# uv-dosimeter-featherwing-mk-1_3.net
KiCad netlist of a schematic drawn in EAGLE
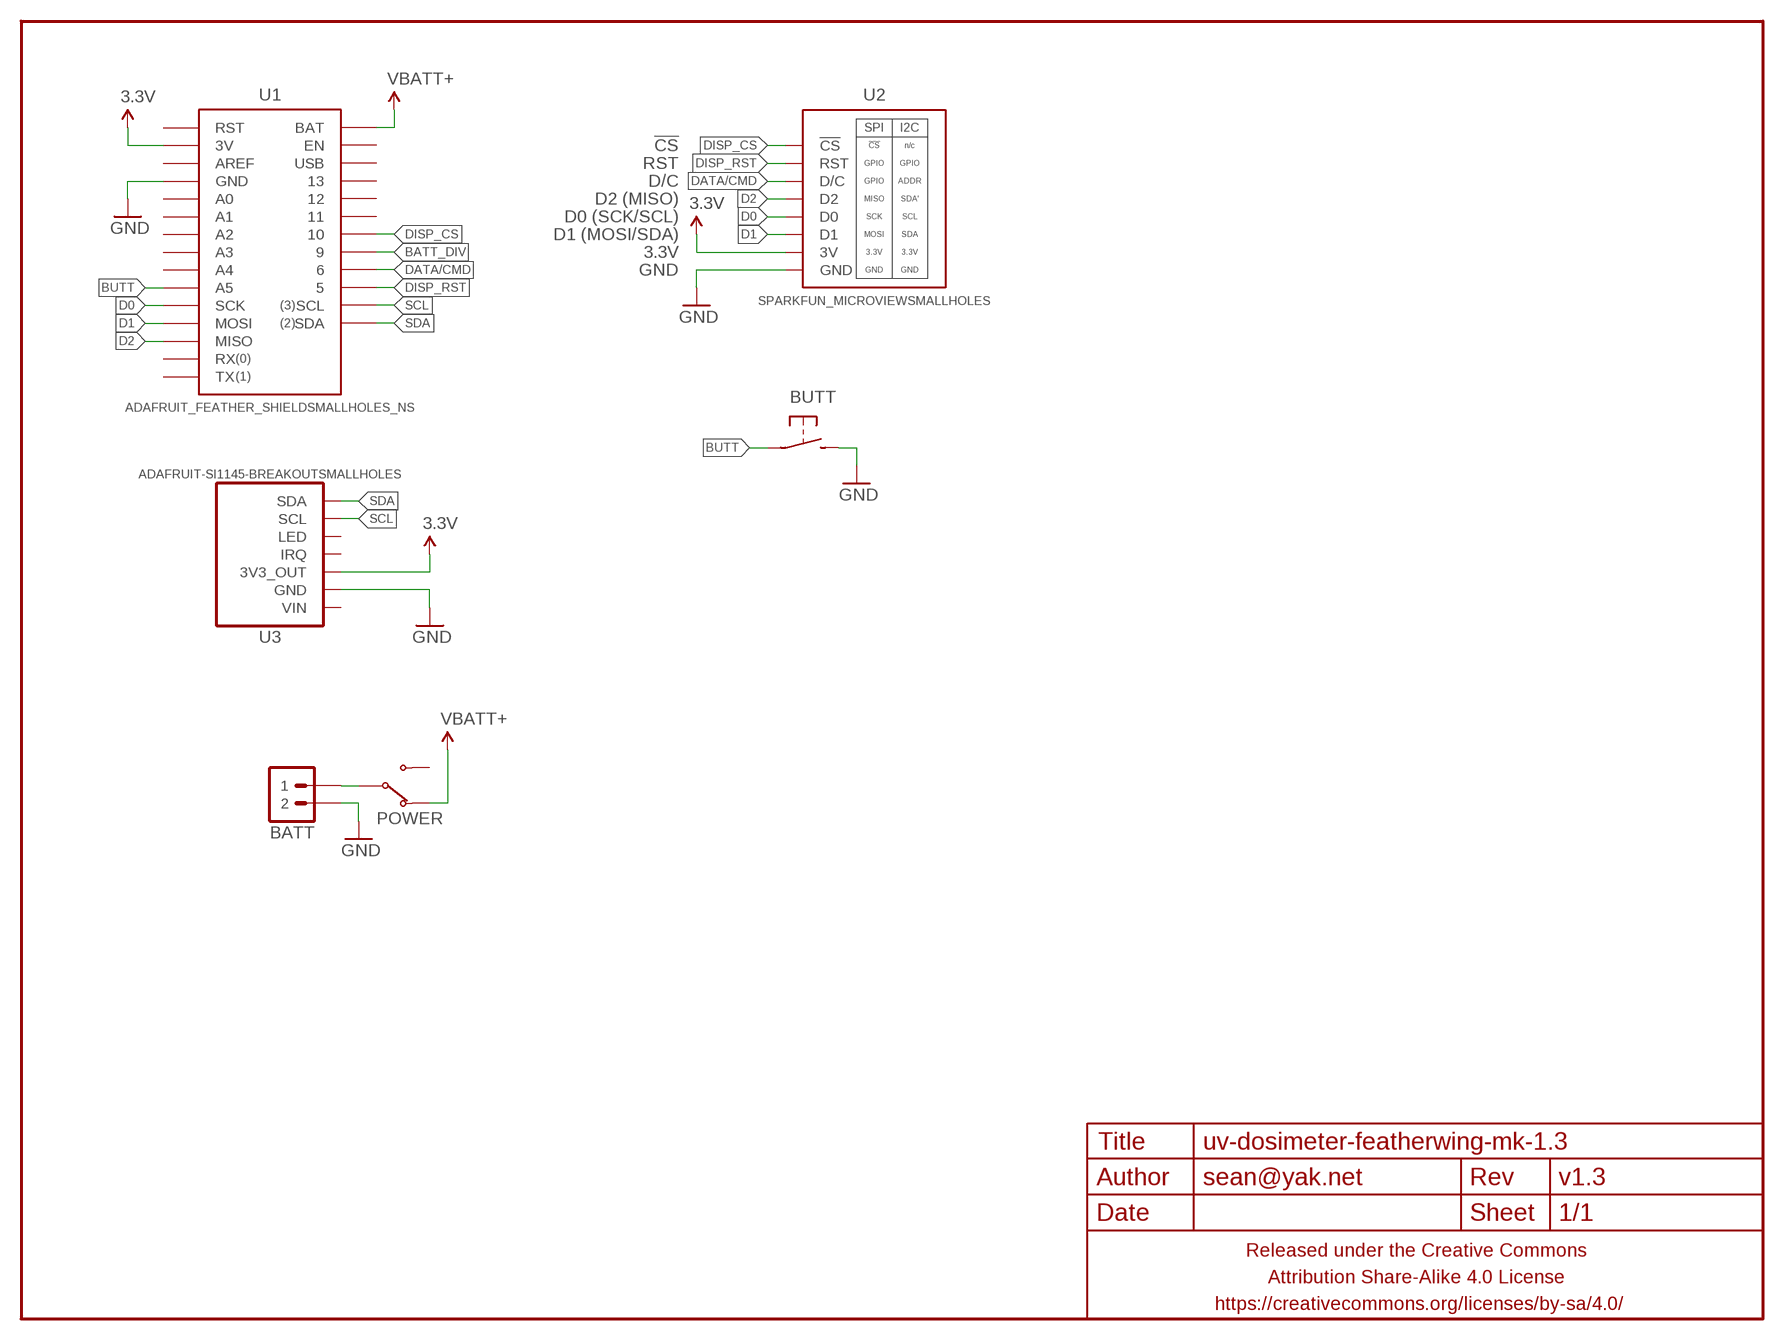
[diagram p0: schematic, sheet 1]

(export (version "E")
  (design (tool "Eeschema 10.0.6"))
  (components
    (comp (ref "BATT")
      (value "M02JST-2MM-SMT")
      (footprint "eagle-import:JST-2-SMD")
      (libsource (lib "eagle-import") (part "M02JST-2MM-SMT"))
    )
    (comp (ref "BUTT")
      (value "SPST-NO-TACT3MM-PTH-SMALL-PADS")
      (footprint "eagle-import:DTS-3-SMALL-PADS")
      (libsource (lib "eagle-import") (part "SPST-NO-TACT3MM-PTH-SMALL-PADS"))
    )
    (comp (ref "FRAME1")
      (value "FRAME-LETTERNO_PACKAGE")
      (footprint "eagle-import:DUMMY")
      (fields (field (name "DESIGNER") "sean@yak.net") (field (name "VERSION") "v1.3"))
      (libsource (lib "eagle-import") (part "FRAME-LETTERNO_PACKAGE"))
    )
    (comp (ref "POWER")
      (value "SWITCH-SPDTPTH-VERT-2.54MM")
      (footprint "eagle-import:SWITCH-SPDT")
      (libsource (lib "eagle-import") (part "SWITCH-SPDTPTH-VERT-2.54MM"))
    )
    (comp (ref "U1")
      (value "ADAFRUIT_FEATHER_SHIELDSMALLHOLES_NS")
      (footprint "eagle-import:ADAFRUIT_FEATHER_SMALLHOLES_NS")
      (libsource (lib "eagle-import") (part "ADAFRUIT_FEATHER_SHIELDSMALLHOLES_NS"))
    )
    (comp (ref "U2")
      (value "SPARKFUN_MICROVIEWSMALLHOLES")
      (footprint "eagle-import:SPARKFUN-MICROVIEW-SMALLHOLES")
      (libsource (lib "eagle-import") (part "SPARKFUN_MICROVIEWSMALLHOLES"))
    )
    (comp (ref "U3")
      (value "ADAFRUIT-SI1145-BREAKOUTSMALLHOLES")
      (footprint "eagle-import:ADAFRUIT-SI1145-BREAKOUT-LESSSILK-SMALLHOLES")
      (libsource (lib "eagle-import") (part "ADAFRUIT-SI1145-BREAKOUTSMALLHOLES"))
    )
  )
  (nets
    (net (code "1") (name "3.3V") (class "Default")
      (node (ref "U1") (pin "3V") (pinfunction "3V_3V") (pintype "bidirectional"))
      (node (ref "U2") (pin "3V") (pinfunction "3V_3V") (pintype "bidirectional"))
      (node (ref "U3") (pin "3V3_OUT") (pinfunction "3V3_OUT_3V3_OUT") (pintype "passive"))
    )
    (net (code "2") (name "BATT_DIV") (class "Default")
      (node (ref "U1") (pin "9") (pinfunction "9_9") (pintype "bidirectional"))
    )
    (net (code "3") (name "BUTT") (class "Default")
      (node (ref "BUTT") (pin "1") (pinfunction "1_1") (pintype "passive"))
      (node (ref "U1") (pin "A5") (pinfunction "A5_A5") (pintype "bidirectional"))
    )
    (net (code "4") (name "D0") (class "Default")
      (node (ref "U1") (pin "SCK") (pinfunction "SCK_SCK") (pintype "bidirectional"))
      (node (ref "U2") (pin "D0") (pinfunction "D0_D0") (pintype "bidirectional"))
    )
    (net (code "5") (name "D1") (class "Default")
      (node (ref "U1") (pin "MOSI") (pinfunction "MOSI_MOSI") (pintype "bidirectional"))
      (node (ref "U2") (pin "D1") (pinfunction "D1_D1") (pintype "bidirectional"))
    )
    (net (code "6") (name "D2") (class "Default")
      (node (ref "U1") (pin "MISO") (pinfunction "MISO_MISO") (pintype "bidirectional"))
      (node (ref "U2") (pin "D2") (pinfunction "D2_D2") (pintype "bidirectional"))
    )
    (net (code "7") (name "DATA{slash}CMD") (class "Default")
      (node (ref "U1") (pin "6") (pinfunction "6_6") (pintype "bidirectional"))
      (node (ref "U2") (pin "D/C") (pinfunction "D/C_D/C") (pintype "bidirectional"))
    )
    (net (code "8") (name "DISP_CS") (class "Default")
      (node (ref "U1") (pin "10") (pinfunction "10_10") (pintype "bidirectional"))
      (node (ref "U2") (pin "CS") (pinfunction "~{CS}_CS") (pintype "bidirectional"))
    )
    (net (code "9") (name "DISP_RST") (class "Default")
      (node (ref "U1") (pin "5") (pinfunction "5_5") (pintype "bidirectional"))
      (node (ref "U2") (pin "RST") (pinfunction "RST_RST") (pintype "bidirectional"))
    )
    (net (code "10") (name "GND") (class "Default")
      (node (ref "BATT") (pin "1") (pinfunction "2_1") (pintype "passive"))
      (node (ref "BUTT") (pin "2") (pinfunction "2_2") (pintype "passive"))
      (node (ref "U1") (pin "GND@0") (pinfunction "GND_GND@0") (pintype "bidirectional"))
      (node (ref "U1") (pin "GND@1") (pinfunction "GND_GND@1") (pintype "bidirectional"))
      (node (ref "U2") (pin "GND") (pinfunction "GND_GND") (pintype "bidirectional"))
      (node (ref "U3") (pin "GND") (pinfunction "GND_GND") (pintype "passive"))
    )
    (net (code "11") (name "Net-(BATT-1)") (class "Default")
      (node (ref "BATT") (pin "2") (pinfunction "1_2") (pintype "passive"))
      (node (ref "POWER") (pin "2") (pinfunction "COM_2") (pintype "passive"))
    )
    (net (code "12") (name "SCL") (class "Default")
      (node (ref "U1") (pin "SCL") (pinfunction "SCL_SCL") (pintype "bidirectional"))
      (node (ref "U3") (pin "SCL") (pinfunction "SCL_SCL") (pintype "passive"))
    )
    (net (code "13") (name "SDA") (class "Default")
      (node (ref "U1") (pin "SDA") (pinfunction "SDA_SDA") (pintype "bidirectional"))
      (node (ref "U3") (pin "SDA") (pinfunction "SDA_SDA") (pintype "passive"))
    )
    (net (code "14") (name "VBATT+") (class "Default")
      (node (ref "POWER") (pin "1") (pinfunction "NC_1") (pintype "passive"))
      (node (ref "U1") (pin "BAT") (pinfunction "BAT_BAT") (pintype "bidirectional"))
    )
    (net (code "15") (name "unconnected-(POWER-NO-Pad3)") (class "Default")
      (node (ref "POWER") (pin "3") (pinfunction "NO_3") (pintype "passive"))
    )
    (net (code "16") (name "unconnected-(U1-Pad11)") (class "Default")
      (node (ref "U1") (pin "11") (pinfunction "11_11") (pintype "bidirectional"))
    )
    (net (code "17") (name "unconnected-(U1-Pad12)") (class "Default")
      (node (ref "U1") (pin "12") (pinfunction "12_12") (pintype "bidirectional"))
    )
    (net (code "18") (name "unconnected-(U1-Pad13)") (class "Default")
      (node (ref "U1") (pin "13") (pinfunction "13_13") (pintype "bidirectional"))
    )
    (net (code "19") (name "unconnected-(U1-PadA0)") (class "Default")
      (node (ref "U1") (pin "A0") (pinfunction "A0_A0") (pintype "bidirectional"))
    )
    (net (code "20") (name "unconnected-(U1-PadA1)") (class "Default")
      (node (ref "U1") (pin "A1") (pinfunction "A1_A1") (pintype "bidirectional"))
    )
    (net (code "21") (name "unconnected-(U1-PadA2)") (class "Default")
      (node (ref "U1") (pin "A2") (pinfunction "A2_A2") (pintype "bidirectional"))
    )
    (net (code "22") (name "unconnected-(U1-PadA3)") (class "Default")
      (node (ref "U1") (pin "A3") (pinfunction "A3_A3") (pintype "bidirectional"))
    )
    (net (code "23") (name "unconnected-(U1-PadA4)") (class "Default")
      (node (ref "U1") (pin "A4") (pinfunction "A4_A4") (pintype "bidirectional"))
    )
    (net (code "24") (name "unconnected-(U1-PadAREF)") (class "Default")
      (node (ref "U1") (pin "AREF") (pinfunction "AREF_AREF") (pintype "bidirectional"))
    )
    (net (code "25") (name "unconnected-(U1-PadEN)") (class "Default")
      (node (ref "U1") (pin "EN") (pinfunction "EN_EN") (pintype "bidirectional"))
    )
    (net (code "26") (name "unconnected-(U1-PadRST)") (class "Default")
      (node (ref "U1") (pin "RST") (pinfunction "RST_RST") (pintype "bidirectional"))
    )
    (net (code "27") (name "unconnected-(U1-PadRX)") (class "Default")
      (node (ref "U1") (pin "RX") (pinfunction "RX_RX") (pintype "bidirectional"))
    )
    (net (code "28") (name "unconnected-(U1-PadTX)") (class "Default")
      (node (ref "U1") (pin "TX") (pinfunction "TX_TX") (pintype "bidirectional"))
    )
    (net (code "29") (name "unconnected-(U1-PadUSB)") (class "Default")
      (node (ref "U1") (pin "USB") (pinfunction "USB_USB") (pintype "bidirectional"))
    )
    (net (code "30") (name "unconnected-(U3-PadIRQ)") (class "Default")
      (node (ref "U3") (pin "IRQ") (pinfunction "IRQ_IRQ") (pintype "passive"))
    )
    (net (code "31") (name "unconnected-(U3-PadLED)") (class "Default")
      (node (ref "U3") (pin "LED") (pinfunction "LED_LED") (pintype "passive"))
    )
    (net (code "32") (name "unconnected-(U3-PadVIN)") (class "Default")
      (node (ref "U3") (pin "VIN") (pinfunction "VIN_VIN") (pintype "passive"))
    )
  )
)
